# mpiv2.net
KiCad netlist of a schematic drawn in Altium Designer
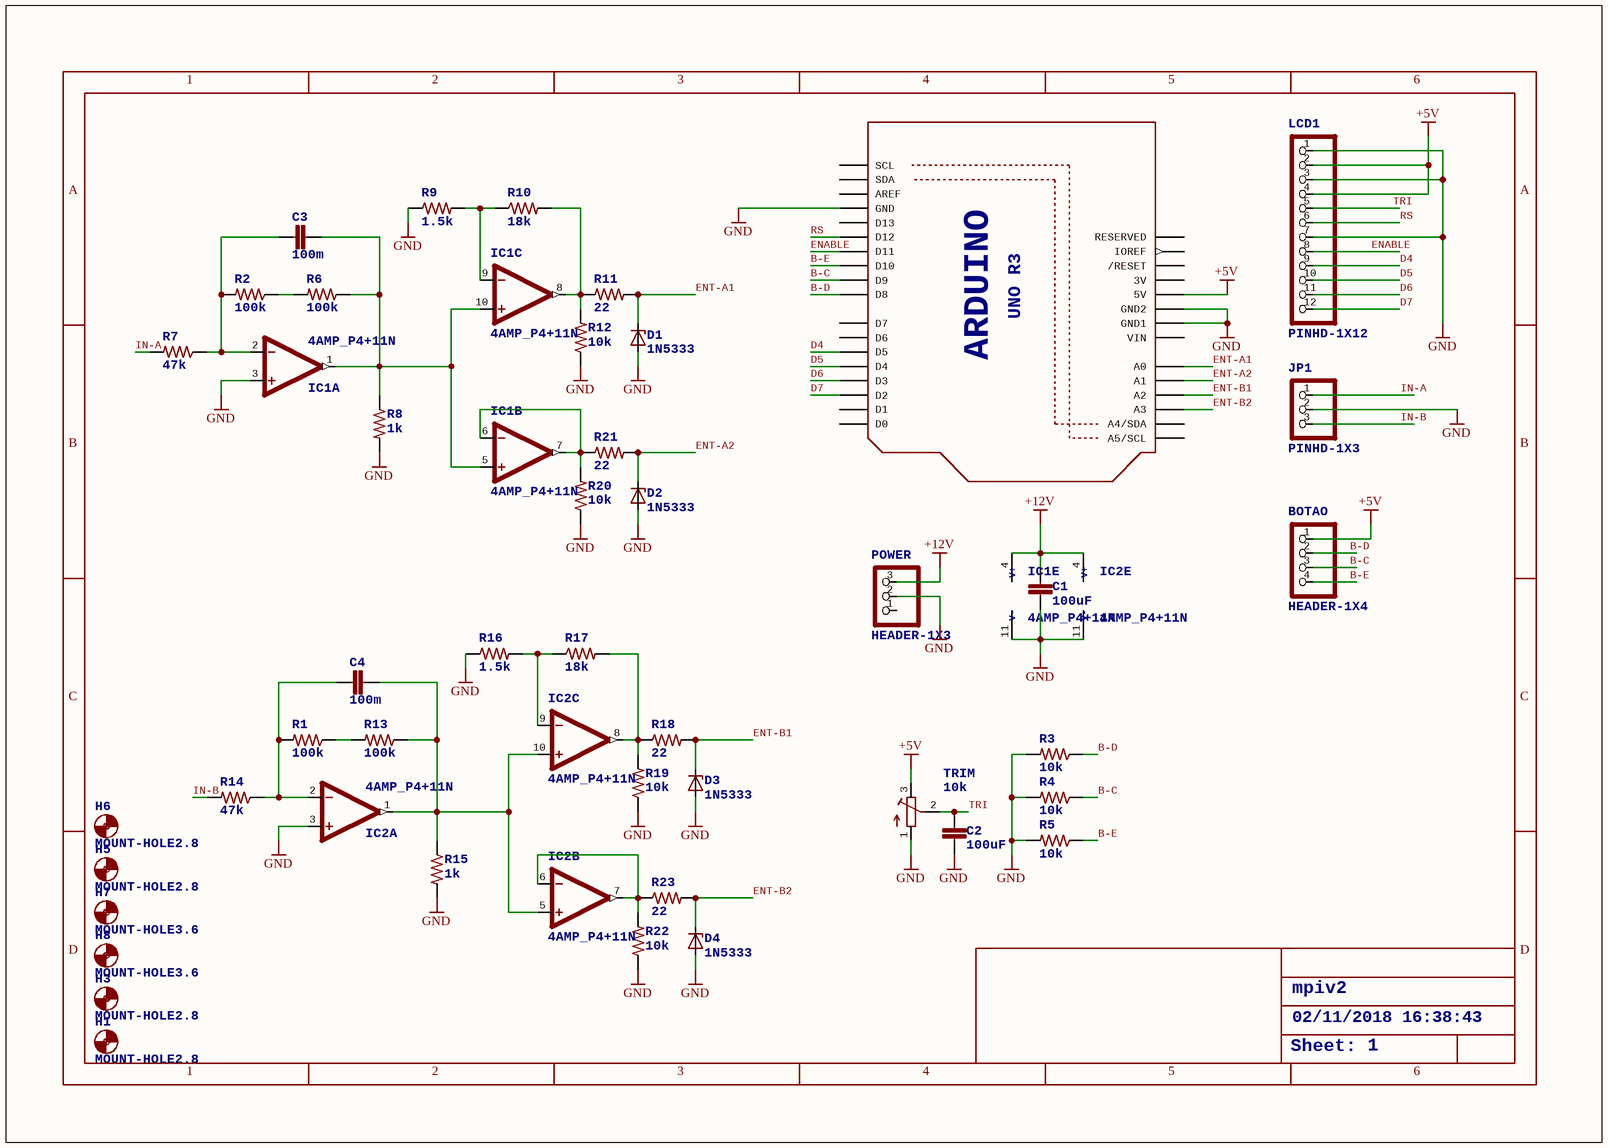
[diagram p0: mpiv2.SchDoc]

(export (version "E")
  (design (tool "Eeschema 10.0.6"))
  (components
    (comp (ref "BOTAO")
      (value "HEADER-1X4")
      (footprint "1X04_OVAL")
      (description "PIN HEADER")
      (libsource (lib "junior") (part "HEADER-1X4"))
    )
    (comp (ref "C1")
      (value "100uF")
      (footprint "C050-035X075")
      (description "CAPACITOR, European symbol")
      (libsource (lib "rcl") (part "C-EU050-035X075"))
    )
    (comp (ref "C2")
      (value "100uF")
      (footprint "C050-035X075")
      (description "CAPACITOR, European symbol")
      (libsource (lib "rcl") (part "C-EU050-035X075"))
    )
    (comp (ref "C3")
      (value "100m")
      (footprint "C075-032X103")
      (description "CAPACITOR, European symbol")
      (libsource (lib "rcl") (part "C-EU075-032X103"))
    )
    (comp (ref "C4")
      (value "100m")
      (footprint "C075-032X103")
      (description "CAPACITOR, European symbol")
      (libsource (lib "rcl") (part "C-EU075-032X103"))
    )
    (comp (ref "D1")
      (value "1N5333")
      (footprint "C1702-15")
      (description "Z DIODE   3.3 V, 5W, 5 percent (Motorola)")
      (libsource (lib "diode") (part "1N5333"))
    )
    (comp (ref "D2")
      (value "1N5333")
      (footprint "C1702-15")
      (description "Z DIODE   3.3 V, 5W, 5 percent (Motorola)")
      (libsource (lib "diode") (part "1N5333"))
    )
    (comp (ref "D3")
      (value "1N5333")
      (footprint "C1702-15")
      (description "Z DIODE   3.3 V, 5W, 5 percent (Motorola)")
      (libsource (lib "diode") (part "1N5333"))
    )
    (comp (ref "D4")
      (value "1N5333")
      (footprint "C1702-15")
      (description "Z DIODE   3.3 V, 5W, 5 percent (Motorola)")
      (libsource (lib "diode") (part "1N5333"))
    )
    (comp (ref "H1")
      (value "MOUNT-HOLE2.8")
      (footprint "2,8")
      (description "MOUNTING HOLE with drill center marker")
      (libsource (lib "holes") (part "MOUNT-HOLE2.8"))
    )
    (comp (ref "H3")
      (value "MOUNT-HOLE2.8")
      (footprint "2,8")
      (description "MOUNTING HOLE with drill center marker")
      (libsource (lib "holes") (part "MOUNT-HOLE2.8"))
    )
    (comp (ref "H5")
      (value "MOUNT-HOLE2.8")
      (footprint "2,8")
      (description "MOUNTING HOLE with drill center marker")
      (libsource (lib "holes") (part "MOUNT-HOLE2.8"))
    )
    (comp (ref "H6")
      (value "MOUNT-HOLE2.8")
      (footprint "2,8")
      (description "MOUNTING HOLE with drill center marker")
      (libsource (lib "holes") (part "MOUNT-HOLE2.8"))
    )
    (comp (ref "H7")
      (value "MOUNT-HOLE3.6")
      (footprint "3,6")
      (description "MOUNTING HOLE with drill center marker")
      (libsource (lib "holes") (part "MOUNT-HOLE3.6"))
    )
    (comp (ref "H8")
      (value "MOUNT-HOLE3.6")
      (footprint "3,6")
      (description "MOUNTING HOLE with drill center marker")
      (libsource (lib "holes") (part "MOUNT-HOLE3.6"))
    )
    (comp (ref "IC1")
      (value "4AMP_P4+11N")
      (footprint "DIL14")
      (description "OP AMP")
      (fields (field (name "V+") "V+") (field (name "V-") "V-"))
      (libsource (lib "linear") (part "4AMP_P4+11N"))
    )
    (comp (ref "IC2")
      (value "4AMP_P4+11N")
      (footprint "DIL14")
      (description "OP AMP")
      (fields (field (name "V+") "V+") (field (name "V-") "V-"))
      (libsource (lib "linear") (part "4AMP_P4+11N"))
    )
    (comp (ref "JP1")
      (value "PINHD-1X3")
      (footprint "1X03")
      (description "PIN HEADER")
      (libsource (lib "pinhead") (part "PINHD-1X3"))
    )
    (comp (ref "LCD1")
      (value "PINHD-1X12")
      (footprint "1X12")
      (description "PIN HEADER")
      (libsource (lib "pinhead") (part "PINHD-1X12"))
    )
    (comp (ref "POWER")
      (value "HEADER-1X3")
      (footprint "1X03_OVAL")
      (description "PIN HEADER")
      (libsource (lib "junior") (part "HEADER-1X3"))
    )
    (comp (ref "R1")
      (value "100k")
      (footprint "0207/10")
      (description "RESISTOR, American symbol")
      (libsource (lib "rcl") (part "R-US_0207/10"))
    )
    (comp (ref "R2")
      (value "100k")
      (footprint "0207/10")
      (description "RESISTOR, American symbol")
      (libsource (lib "rcl") (part "R-US_0207/10"))
    )
    (comp (ref "R3")
      (value "10k")
      (footprint "0207/10")
      (description "RESISTOR, American symbol")
      (libsource (lib "rcl") (part "R-US_0207/10"))
    )
    (comp (ref "R4")
      (value "10k")
      (footprint "0207/10")
      (description "RESISTOR, American symbol")
      (libsource (lib "rcl") (part "R-US_0207/10"))
    )
    (comp (ref "R5")
      (value "10k")
      (footprint "0207/10")
      (description "RESISTOR, American symbol")
      (libsource (lib "rcl") (part "R-US_0207/10"))
    )
    (comp (ref "R6")
      (value "100k")
      (footprint "0207/10")
      (description "RESISTOR, American symbol")
      (libsource (lib "rcl") (part "R-US_0207/10"))
    )
    (comp (ref "R7")
      (value "47k")
      (footprint "0207/10")
      (description "RESISTOR, American symbol")
      (libsource (lib "rcl") (part "R-US_0207/10"))
    )
    (comp (ref "R8")
      (value "1k")
      (footprint "0207/10")
      (description "RESISTOR, American symbol")
      (libsource (lib "rcl") (part "R-US_0207/10"))
    )
    (comp (ref "R9")
      (value "1.5k")
      (footprint "0207/10")
      (description "RESISTOR, American symbol")
      (libsource (lib "rcl") (part "R-US_0207/10"))
    )
    (comp (ref "R10")
      (value "18k")
      (footprint "0207/10")
      (description "RESISTOR, American symbol")
      (libsource (lib "rcl") (part "R-US_0207/10"))
    )
    (comp (ref "R11")
      (value "22")
      (footprint "0207/10")
      (description "RESISTOR, American symbol")
      (libsource (lib "rcl") (part "R-US_0207/10"))
    )
    (comp (ref "R12")
      (value "10k")
      (footprint "0207/10")
      (description "RESISTOR, American symbol")
      (libsource (lib "rcl") (part "R-US_0207/10"))
    )
    (comp (ref "R13")
      (value "100k")
      (footprint "0207/10")
      (description "RESISTOR, American symbol")
      (libsource (lib "rcl") (part "R-US_0207/10"))
    )
    (comp (ref "R14")
      (value "47k")
      (footprint "0207/10")
      (description "RESISTOR, American symbol")
      (libsource (lib "rcl") (part "R-US_0207/10"))
    )
    (comp (ref "R15")
      (value "1k")
      (footprint "0207/10")
      (description "RESISTOR, American symbol")
      (libsource (lib "rcl") (part "R-US_0207/10"))
    )
    (comp (ref "R16")
      (value "1.5k")
      (footprint "0207/10")
      (description "RESISTOR, American symbol")
      (libsource (lib "rcl") (part "R-US_0207/10"))
    )
    (comp (ref "R17")
      (value "18k")
      (footprint "0207/10")
      (description "RESISTOR, American symbol")
      (libsource (lib "rcl") (part "R-US_0207/10"))
    )
    (comp (ref "R18")
      (value "22")
      (footprint "0207/10")
      (description "RESISTOR, American symbol")
      (libsource (lib "rcl") (part "R-US_0207/10"))
    )
    (comp (ref "R19")
      (value "10k")
      (footprint "0207/10")
      (description "RESISTOR, American symbol")
      (libsource (lib "rcl") (part "R-US_0207/10"))
    )
    (comp (ref "R20")
      (value "10k")
      (footprint "0207/10")
      (description "RESISTOR, American symbol")
      (libsource (lib "rcl") (part "R-US_0207/10"))
    )
    (comp (ref "R21")
      (value "22")
      (footprint "0207/10")
      (description "RESISTOR, American symbol")
      (libsource (lib "rcl") (part "R-US_0207/10"))
    )
    (comp (ref "R22")
      (value "10k")
      (footprint "0207/10")
      (description "RESISTOR, American symbol")
      (libsource (lib "rcl") (part "R-US_0207/10"))
    )
    (comp (ref "R23")
      (value "22")
      (footprint "0207/10")
      (description "RESISTOR, American symbol")
      (libsource (lib "rcl") (part "R-US_0207/10"))
    )
    (comp (ref "TRIM")
      (value "10k")
      (footprint "RTRIM74W")
      (description "Trimm resistor")
      (libsource (lib "resistor") (part "R-TRIMM74W"))
    )
    (comp (ref "U1")
      (value "ARDUINOR3-BPLACE")
      (footprint "ARDUINOR3-BPLACE")
      (fields (field (name "ARDUINO") "ARDUINO") (field (name "UNOR3") "UNO R3"))
      (libsource (lib "junior") (part "ARDUINOR3-BPLACE"))
    )
  )
  (nets
    (net (code "1") (name "+5V") (class "Default")
      (node (ref "BOTAO") (pin "1") (pinfunction "1_1") (pintype "passive"))
      (node (ref "LCD1") (pin "2") (pinfunction "2_2") (pintype "passive"))
      (node (ref "LCD1") (pin "4") (pinfunction "4_4") (pintype "passive"))
      (node (ref "TRIM") (pin "3") (pinfunction "A_3") (pintype "passive"))
      (node (ref "U1") (pin "5V") (pinfunction "5V_5V") (pintype "power_in"))
    )
    (net (code "2") (name "+12V") (class "Default")
      (node (ref "C1") (pin "1") (pinfunction "1_1") (pintype "passive"))
      (node (ref "IC1") (pin "4") (pinfunction "V+_4") (pintype "power_in"))
      (node (ref "IC2") (pin "4") (pinfunction "V+_4") (pintype "power_in"))
      (node (ref "POWER") (pin "3") (pinfunction "3_3") (pintype "passive"))
    )
    (net (code "3") (name "/B-C") (class "Default")
      (node (ref "BOTAO") (pin "3") (pinfunction "3_3") (pintype "passive"))
      (node (ref "R4") (pin "1") (pinfunction "1_1") (pintype "passive"))
      (node (ref "U1") (pin "D9") (pinfunction "D9_D9") (pintype "passive"))
    )
    (net (code "4") (name "/B-D") (class "Default")
      (node (ref "BOTAO") (pin "2") (pinfunction "2_2") (pintype "passive"))
      (node (ref "R3") (pin "1") (pinfunction "1_1") (pintype "passive"))
      (node (ref "U1") (pin "D8") (pinfunction "D8_D8") (pintype "passive"))
    )
    (net (code "5") (name "/B-E") (class "Default")
      (node (ref "BOTAO") (pin "4") (pinfunction "4_4") (pintype "passive"))
      (node (ref "R5") (pin "1") (pinfunction "1_1") (pintype "passive"))
      (node (ref "U1") (pin "D10") (pinfunction "D10_D10") (pintype "passive"))
    )
    (net (code "6") (name "/D4") (class "Default")
      (node (ref "LCD1") (pin "9") (pinfunction "9_9") (pintype "passive"))
      (node (ref "U1") (pin "D5") (pinfunction "D5_D5") (pintype "passive"))
    )
    (net (code "7") (name "/D5") (class "Default")
      (node (ref "LCD1") (pin "10") (pinfunction "10_10") (pintype "passive"))
      (node (ref "U1") (pin "D4") (pinfunction "D4_D4") (pintype "passive"))
    )
    (net (code "8") (name "/D6") (class "Default")
      (node (ref "LCD1") (pin "11") (pinfunction "11_11") (pintype "passive"))
      (node (ref "U1") (pin "D3") (pinfunction "D3_D3") (pintype "passive"))
    )
    (net (code "9") (name "/D7") (class "Default")
      (node (ref "LCD1") (pin "12") (pinfunction "12_12") (pintype "passive"))
      (node (ref "U1") (pin "D2") (pinfunction "D2_D2") (pintype "passive"))
    )
    (net (code "10") (name "/ENABLE") (class "Default")
      (node (ref "LCD1") (pin "8") (pinfunction "8_8") (pintype "passive"))
      (node (ref "U1") (pin "D11") (pinfunction "D11_D11") (pintype "passive"))
    )
    (net (code "11") (name "/ENT-A1") (class "Default")
      (node (ref "D1") (pin "C") (pinfunction "C_C") (pintype "passive"))
      (node (ref "R11") (pin "2") (pinfunction "2_2") (pintype "passive"))
      (node (ref "U1") (pin "A0") (pinfunction "A0_A0") (pintype "passive"))
    )
    (net (code "12") (name "/ENT-A2") (class "Default")
      (node (ref "D2") (pin "C") (pinfunction "C_C") (pintype "passive"))
      (node (ref "R21") (pin "2") (pinfunction "2_2") (pintype "passive"))
      (node (ref "U1") (pin "A1") (pinfunction "A1_A1") (pintype "passive"))
    )
    (net (code "13") (name "/ENT-B1") (class "Default")
      (node (ref "D3") (pin "C") (pinfunction "C_C") (pintype "passive"))
      (node (ref "R18") (pin "2") (pinfunction "2_2") (pintype "passive"))
      (node (ref "U1") (pin "A2") (pinfunction "A2_A2") (pintype "passive"))
    )
    (net (code "14") (name "/ENT-B2") (class "Default")
      (node (ref "D4") (pin "C") (pinfunction "C_C") (pintype "passive"))
      (node (ref "R23") (pin "2") (pinfunction "2_2") (pintype "passive"))
      (node (ref "U1") (pin "A3") (pinfunction "A3_A3") (pintype "passive"))
    )
    (net (code "15") (name "/IN-A") (class "Default")
      (node (ref "JP1") (pin "1") (pinfunction "1_1") (pintype "passive"))
      (node (ref "R7") (pin "2") (pinfunction "2_2") (pintype "passive"))
    )
    (net (code "16") (name "/IN-B") (class "Default")
      (node (ref "JP1") (pin "3") (pinfunction "3_3") (pintype "passive"))
      (node (ref "R14") (pin "2") (pinfunction "2_2") (pintype "passive"))
    )
    (net (code "17") (name "/RS") (class "Default")
      (node (ref "LCD1") (pin "6") (pinfunction "6_6") (pintype "passive"))
      (node (ref "U1") (pin "D12") (pinfunction "D12_D12") (pintype "passive"))
    )
    (net (code "18") (name "/TRI") (class "Default")
      (node (ref "C2") (pin "1") (pinfunction "1_1") (pintype "passive"))
      (node (ref "LCD1") (pin "5") (pinfunction "5_5") (pintype "passive"))
      (node (ref "TRIM") (pin "2") (pinfunction "S_2") (pintype "passive"))
    )
    (net (code "19") (name "GND") (class "Default")
      (node (ref "C1") (pin "2") (pinfunction "2_2") (pintype "passive"))
      (node (ref "C2") (pin "2") (pinfunction "2_2") (pintype "passive"))
      (node (ref "D1") (pin "A") (pinfunction "A_A") (pintype "passive"))
      (node (ref "D2") (pin "A") (pinfunction "A_A") (pintype "passive"))
      (node (ref "D3") (pin "A") (pinfunction "A_A") (pintype "passive"))
      (node (ref "D4") (pin "A") (pinfunction "A_A") (pintype "passive"))
      (node (ref "IC1") (pin "11") (pinfunction "V-_11") (pintype "power_in"))
      (node (ref "IC1") (pin "3") (pinfunction "+IN_3") (pintype "passive"))
      (node (ref "IC2") (pin "11") (pinfunction "V-_11") (pintype "power_in"))
      (node (ref "IC2") (pin "3") (pinfunction "+IN_3") (pintype "passive"))
      (node (ref "JP1") (pin "2") (pinfunction "2_2") (pintype "passive"))
      (node (ref "LCD1") (pin "1") (pinfunction "1_1") (pintype "passive"))
      (node (ref "LCD1") (pin "3") (pinfunction "3_3") (pintype "passive"))
      (node (ref "LCD1") (pin "7") (pinfunction "7_7") (pintype "passive"))
      (node (ref "POWER") (pin "2") (pinfunction "2_2") (pintype "passive"))
      (node (ref "R12") (pin "1") (pinfunction "1_1") (pintype "passive"))
      (node (ref "R15") (pin "2") (pinfunction "2_2") (pintype "passive"))
      (node (ref "R16") (pin "1") (pinfunction "1_1") (pintype "passive"))
      (node (ref "R19") (pin "1") (pinfunction "1_1") (pintype "passive"))
      (node (ref "R20") (pin "1") (pinfunction "1_1") (pintype "passive"))
      (node (ref "R22") (pin "1") (pinfunction "1_1") (pintype "passive"))
      (node (ref "R3") (pin "2") (pinfunction "2_2") (pintype "passive"))
      (node (ref "R4") (pin "2") (pinfunction "2_2") (pintype "passive"))
      (node (ref "R5") (pin "2") (pinfunction "2_2") (pintype "passive"))
      (node (ref "R8") (pin "2") (pinfunction "2_2") (pintype "passive"))
      (node (ref "R9") (pin "1") (pinfunction "1_1") (pintype "passive"))
      (node (ref "TRIM") (pin "1") (pinfunction "E_1") (pintype "passive"))
      (node (ref "U1") (pin "GND") (pinfunction "GND_GND") (pintype "power_in"))
      (node (ref "U1") (pin "GND1") (pinfunction "GND1_GND1") (pintype "power_in"))
      (node (ref "U1") (pin "GND2") (pinfunction "GND2_GND2") (pintype "power_in"))
    )
    (net (code "20") (name "Net-(IC1A--IN)") (class "Default")
      (node (ref "C3") (pin "1") (pinfunction "1_1") (pintype "passive"))
      (node (ref "IC1") (pin "2") (pinfunction "-IN_2") (pintype "passive"))
      (node (ref "R2") (pin "2") (pinfunction "2_2") (pintype "passive"))
      (node (ref "R7") (pin "1") (pinfunction "1_1") (pintype "passive"))
    )
    (net (code "21") (name "Net-(IC1A-OUT)") (class "Default")
      (node (ref "C3") (pin "2") (pinfunction "2_2") (pintype "passive"))
      (node (ref "IC1") (pin "1") (pinfunction "OUT_1") (pintype "output"))
      (node (ref "IC1") (pin "10") (pinfunction "+IN_10") (pintype "passive"))
      (node (ref "IC1") (pin "5") (pinfunction "+IN_5") (pintype "passive"))
      (node (ref "R6") (pin "1") (pinfunction "1_1") (pintype "passive"))
      (node (ref "R8") (pin "1") (pinfunction "1_1") (pintype "passive"))
    )
    (net (code "22") (name "Net-(IC1B--IN)") (class "Default")
      (node (ref "IC1") (pin "6") (pinfunction "-IN_6") (pintype "passive"))
      (node (ref "IC1") (pin "7") (pinfunction "OUT_7") (pintype "output"))
      (node (ref "R20") (pin "2") (pinfunction "2_2") (pintype "passive"))
      (node (ref "R21") (pin "1") (pinfunction "1_1") (pintype "passive"))
    )
    (net (code "23") (name "Net-(IC1C--IN)") (class "Default")
      (node (ref "IC1") (pin "9") (pinfunction "-IN_9") (pintype "passive"))
      (node (ref "R10") (pin "1") (pinfunction "1_1") (pintype "passive"))
      (node (ref "R9") (pin "2") (pinfunction "2_2") (pintype "passive"))
    )
    (net (code "24") (name "Net-(IC1C-OUT)") (class "Default")
      (node (ref "IC1") (pin "8") (pinfunction "OUT_8") (pintype "output"))
      (node (ref "R10") (pin "2") (pinfunction "2_2") (pintype "passive"))
      (node (ref "R11") (pin "1") (pinfunction "1_1") (pintype "passive"))
      (node (ref "R12") (pin "2") (pinfunction "2_2") (pintype "passive"))
    )
    (net (code "25") (name "Net-(IC2A--IN)") (class "Default")
      (node (ref "C4") (pin "1") (pinfunction "1_1") (pintype "passive"))
      (node (ref "IC2") (pin "2") (pinfunction "-IN_2") (pintype "passive"))
      (node (ref "R1") (pin "2") (pinfunction "2_2") (pintype "passive"))
      (node (ref "R14") (pin "1") (pinfunction "1_1") (pintype "passive"))
    )
    (net (code "26") (name "Net-(IC2A-OUT)") (class "Default")
      (node (ref "C4") (pin "2") (pinfunction "2_2") (pintype "passive"))
      (node (ref "IC2") (pin "1") (pinfunction "OUT_1") (pintype "output"))
      (node (ref "IC2") (pin "10") (pinfunction "+IN_10") (pintype "passive"))
      (node (ref "IC2") (pin "5") (pinfunction "+IN_5") (pintype "passive"))
      (node (ref "R13") (pin "1") (pinfunction "1_1") (pintype "passive"))
      (node (ref "R15") (pin "1") (pinfunction "1_1") (pintype "passive"))
    )
    (net (code "27") (name "Net-(IC2B--IN)") (class "Default")
      (node (ref "IC2") (pin "6") (pinfunction "-IN_6") (pintype "passive"))
      (node (ref "IC2") (pin "7") (pinfunction "OUT_7") (pintype "output"))
      (node (ref "R22") (pin "2") (pinfunction "2_2") (pintype "passive"))
      (node (ref "R23") (pin "1") (pinfunction "1_1") (pintype "passive"))
    )
    (net (code "28") (name "Net-(IC2C--IN)") (class "Default")
      (node (ref "IC2") (pin "9") (pinfunction "-IN_9") (pintype "passive"))
      (node (ref "R16") (pin "2") (pinfunction "2_2") (pintype "passive"))
      (node (ref "R17") (pin "1") (pinfunction "1_1") (pintype "passive"))
    )
    (net (code "29") (name "Net-(IC2C-OUT)") (class "Default")
      (node (ref "IC2") (pin "8") (pinfunction "OUT_8") (pintype "output"))
      (node (ref "R17") (pin "2") (pinfunction "2_2") (pintype "passive"))
      (node (ref "R18") (pin "1") (pinfunction "1_1") (pintype "passive"))
      (node (ref "R19") (pin "2") (pinfunction "2_2") (pintype "passive"))
    )
    (net (code "30") (name "Net-(R1-Pad1)") (class "Default")
      (node (ref "R1") (pin "1") (pinfunction "1_1") (pintype "passive"))
      (node (ref "R13") (pin "2") (pinfunction "2_2") (pintype "passive"))
    )
    (net (code "31") (name "Net-(R2-Pad1)") (class "Default")
      (node (ref "R2") (pin "1") (pinfunction "1_1") (pintype "passive"))
      (node (ref "R6") (pin "2") (pinfunction "2_2") (pintype "passive"))
    )
    (net (code "32") (name "unconnected-(POWER-Pad1)") (class "Default")
      (node (ref "POWER") (pin "1") (pinfunction "1_1") (pintype "passive"))
    )
    (net (code "33") (name "unconnected-(U1-A4{slash}SDA-PadA4)") (class "Default")
      (node (ref "U1") (pin "A4") (pinfunction "A4/SDA_A4") (pintype "passive"))
    )
    (net (code "34") (name "unconnected-(U1-A5{slash}SCL-PadA5)") (class "Default")
      (node (ref "U1") (pin "A5") (pinfunction "A5/SCL_A5") (pintype "passive"))
    )
    (net (code "35") (name "unconnected-(U1-Pad3V)") (class "Default")
      (node (ref "U1") (pin "3V") (pinfunction "3V_3V") (pintype "power_in"))
    )
    (net (code "36") (name "unconnected-(U1-PadAREF)") (class "Default")
      (node (ref "U1") (pin "AREF") (pinfunction "AREF_AREF") (pintype "passive"))
    )
    (net (code "37") (name "unconnected-(U1-PadD0)") (class "Default")
      (node (ref "U1") (pin "D0") (pinfunction "D0_D0") (pintype "passive"))
    )
    (net (code "38") (name "unconnected-(U1-PadD1)") (class "Default")
      (node (ref "U1") (pin "D1") (pinfunction "D1_D1") (pintype "passive"))
    )
    (net (code "39") (name "unconnected-(U1-PadD6)") (class "Default")
      (node (ref "U1") (pin "D6") (pinfunction "D6_D6") (pintype "passive"))
    )
    (net (code "40") (name "unconnected-(U1-PadD7)") (class "Default")
      (node (ref "U1") (pin "D7") (pinfunction "D7_D7") (pintype "passive"))
    )
    (net (code "41") (name "unconnected-(U1-PadD13)") (class "Default")
      (node (ref "U1") (pin "D13") (pinfunction "D13_D13") (pintype "passive"))
    )
    (net (code "42") (name "unconnected-(U1-PadIOREF)") (class "Default")
      (node (ref "U1") (pin "IOREF") (pinfunction "IOREF_IOREF") (pintype "output"))
    )
    (net (code "43") (name "unconnected-(U1-PadRESERVED)") (class "Default")
      (node (ref "U1") (pin "RESERVED") (pinfunction "RESERVED_RESERVED") (pintype "passive"))
    )
    (net (code "44") (name "unconnected-(U1-PadSCL)") (class "Default")
      (node (ref "U1") (pin "SCL") (pinfunction "SCL_SCL") (pintype "passive"))
    )
    (net (code "45") (name "unconnected-(U1-PadSDA)") (class "Default")
      (node (ref "U1") (pin "SDA") (pinfunction "SDA_SDA") (pintype "passive"))
    )
    (net (code "46") (name "unconnected-(U1-PadVIN)") (class "Default")
      (node (ref "U1") (pin "VIN") (pinfunction "VIN_VIN") (pintype "power_in"))
    )
    (net (code "47") (name "unconnected-(U1-{slash}RESET-PadRESET)") (class "Default")
      (node (ref "U1") (pin "RESET") (pinfunction "/RESET_RESET") (pintype "passive"))
    )
  )
)
